# SparkFun_XBee_Arduino_Shield_Qwiic.net
KiCad netlist of a schematic drawn in EAGLE
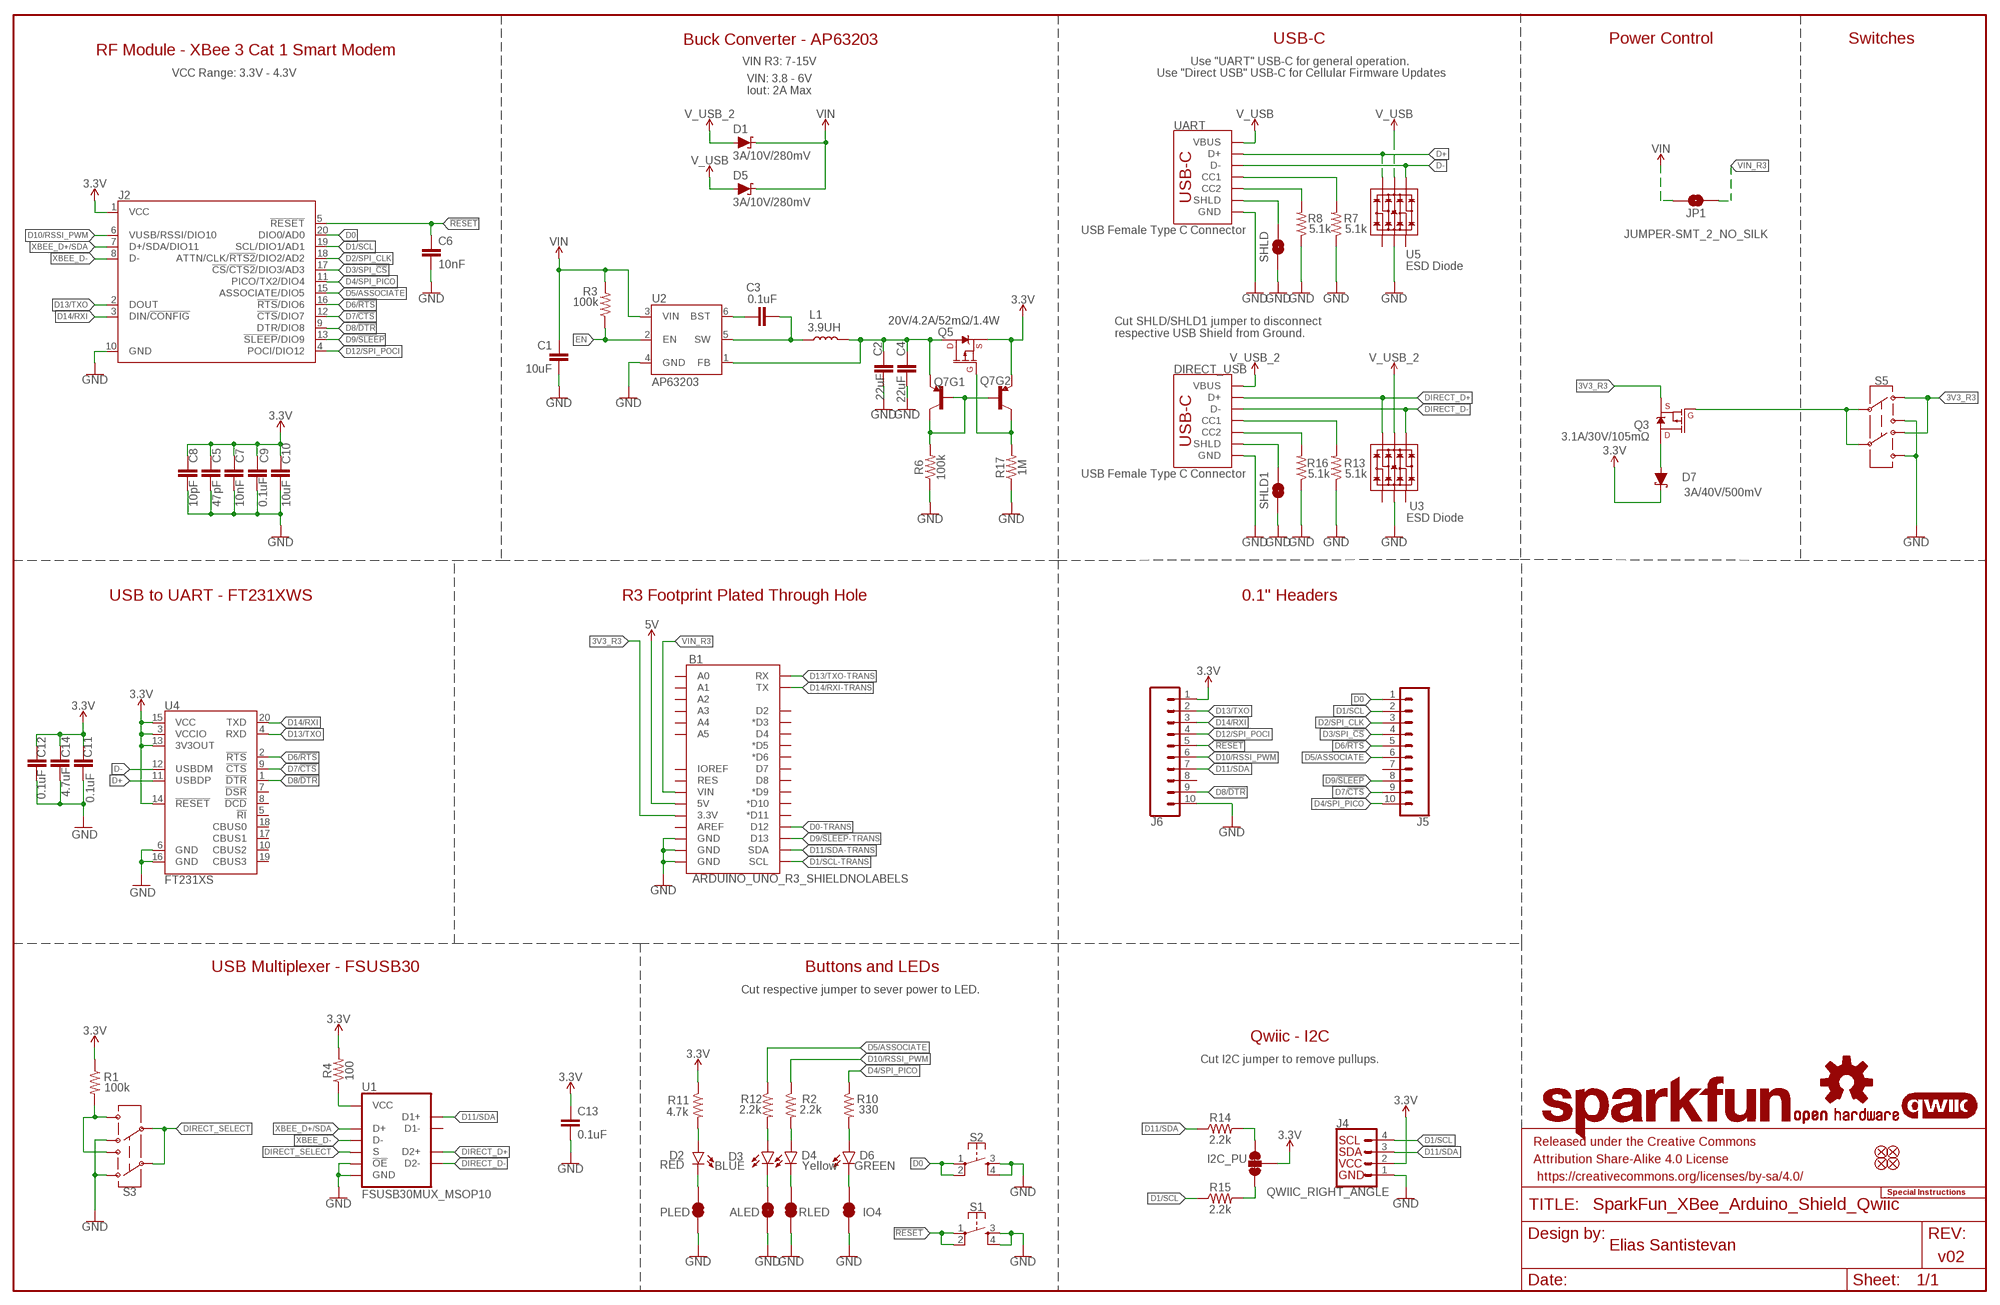
[diagram p0: schematic, sheet 1]

(export (version "E")
  (design (tool "Eeschema 10.0.6"))
  (components
    (comp (ref "ALED")
      (value "JUMPER-SMT_2_NC_TRACE_SILK")
      (footprint "eagle-import:SMT-JUMPER_2_NC_TRACE_SILK")
      (libsource (lib "eagle-import") (part "JUMPER-SMT_2_NC_TRACE_SILK"))
    )
    (comp (ref "B1")
      (value "ARDUINO_UNO_R3_SHIELDNOLABELS")
      (footprint "eagle-import:UNO_R3_SHIELD_NOLABELS")
      (libsource (lib "eagle-import") (part "ARDUINO_UNO_R3_SHIELDNOLABELS"))
    )
    (comp (ref "C1")
      (value "10uF")
      (footprint "eagle-import:1210")
      (libsource (lib "eagle-import") (part "10UF-1210-50V-20%"))
    )
    (comp (ref "C2")
      (value "22uF")
      (footprint "eagle-import:0603")
      (libsource (lib "eagle-import") (part "22UF-0603-6.3V-20%"))
    )
    (comp (ref "C3")
      (value "0.1uF")
      (footprint "eagle-import:0603")
      (libsource (lib "eagle-import") (part "0.1UF-0603-25V-5%"))
    )
    (comp (ref "C4")
      (value "22uF")
      (footprint "eagle-import:0603")
      (libsource (lib "eagle-import") (part "22UF-0603-6.3V-20%"))
    )
    (comp (ref "C5")
      (value "47pF")
      (footprint "eagle-import:0603")
      (libsource (lib "eagle-import") (part "47PF-0603-50V-5%"))
    )
    (comp (ref "C6")
      (value "10nF")
      (footprint "eagle-import:0603")
      (libsource (lib "eagle-import") (part "10NF-0603-50V-10%"))
    )
    (comp (ref "C7")
      (value "10nF")
      (footprint "eagle-import:0603")
      (libsource (lib "eagle-import") (part "10NF-0603-50V-10%"))
    )
    (comp (ref "C8")
      (value "10pF")
      (footprint "eagle-import:0603")
      (libsource (lib "eagle-import") (part "10PF-0603-50V-5%"))
    )
    (comp (ref "C9")
      (value "0.1uF")
      (footprint "eagle-import:0603")
      (libsource (lib "eagle-import") (part "0.1UF-0603-25V-(+80/-20%)"))
    )
    (comp (ref "C10")
      (value "10uF")
      (footprint "eagle-import:0603")
      (libsource (lib "eagle-import") (part "10UF-0603-6.3V-20%"))
    )
    (comp (ref "C11")
      (value "0.1uF")
      (footprint "eagle-import:0603")
      (libsource (lib "eagle-import") (part "0.1UF-0603-25V-(+80/-20%)"))
    )
    (comp (ref "C12")
      (value "0.1uF")
      (footprint "eagle-import:0603")
      (libsource (lib "eagle-import") (part "0.1UF-0603-25V-(+80/-20%)"))
    )
    (comp (ref "C13")
      (value "0.1uF")
      (footprint "eagle-import:0603")
      (libsource (lib "eagle-import") (part "0.1UF-0603-25V-(+80/-20%)"))
    )
    (comp (ref "C14")
      (value "4.7uF")
      (footprint "eagle-import:0603")
      (libsource (lib "eagle-import") (part "4.7UF-0603-6.3V-(10%)"))
    )
    (comp (ref "D1")
      (value "3A/10V/280mV")
      (footprint "eagle-import:SOD-323")
      (libsource (lib "eagle-import") (part "DIODE-SCHOTTKY-BAT60A"))
    )
    (comp (ref "D2")
      (value "RED")
      (footprint "eagle-import:LED-0603")
      (libsource (lib "eagle-import") (part "LED-RED_0603-KB"))
    )
    (comp (ref "D3")
      (value "BLUE")
      (footprint "eagle-import:LED-0603")
      (libsource (lib "eagle-import") (part "LED-BLUE0603"))
    )
    (comp (ref "D4")
      (value "Yellow")
      (footprint "eagle-import:LED-0603")
      (libsource (lib "eagle-import") (part "LED-YELLOW0603"))
    )
    (comp (ref "D5")
      (value "3A/10V/280mV")
      (footprint "eagle-import:SOD-323")
      (libsource (lib "eagle-import") (part "DIODE-SCHOTTKY-BAT60A"))
    )
    (comp (ref "D6")
      (value "GREEN")
      (footprint "eagle-import:LED-0603")
      (libsource (lib "eagle-import") (part "LED-GREEN0603"))
    )
    (comp (ref "D7")
      (value "3A/40V/500mV")
      (footprint "eagle-import:SMA-DIODE")
      (libsource (lib "eagle-import") (part "DIODE-SCHOTTKY-B340A"))
    )
    (comp (ref "DIRECT_USB")
      (value "USB Female Type C Connector")
      (footprint "eagle-import:USB-C-16P-4LAYER-ISOLATED")
      (libsource (lib "eagle-import") (part "USB_C_4-LAYER-ISOLATED"))
    )
    (comp (ref "FD1")
      (value "FIDUCIAL1X2")
      (footprint "eagle-import:FIDUCIAL-1X2")
      (libsource (lib "eagle-import") (part "FIDUCIAL1X2"))
    )
    (comp (ref "FD2")
      (value "FIDUCIAL1X2")
      (footprint "eagle-import:FIDUCIAL-1X2")
      (libsource (lib "eagle-import") (part "FIDUCIAL1X2"))
    )
    (comp (ref "FD3")
      (value "FIDUCIAL1X2")
      (footprint "eagle-import:FIDUCIAL-1X2")
      (libsource (lib "eagle-import") (part "FIDUCIAL1X2"))
    )
    (comp (ref "FD4")
      (value "FIDUCIAL1X2")
      (footprint "eagle-import:FIDUCIAL-1X2")
      (libsource (lib "eagle-import") (part "FIDUCIAL1X2"))
    )
    (comp (ref "FRAME1")
      (value "FRAME-LEDGER")
      (footprint "eagle-import:CREATIVE_COMMONS")
      (libsource (lib "eagle-import") (part "FRAME-LEDGER"))
    )
    (comp (ref "I2C_PU")
      (value "JUMPER-SMT_3_2-NC_TRACE_SILK")
      (footprint "eagle-import:SMT-JUMPER_3_2-NC_TRACE_SILK")
      (libsource (lib "eagle-import") (part "JUMPER-SMT_3_2-NC_TRACE_SILK"))
    )
    (comp (ref "IO4")
      (value "JUMPER-SMT_2_NC_TRACE_SILK")
      (footprint "eagle-import:SMT-JUMPER_2_NC_TRACE_SILK")
      (libsource (lib "eagle-import") (part "JUMPER-SMT_2_NC_TRACE_SILK"))
    )
    (comp (ref "J2")
      (value "XBEE_UPDATEXBEE_SMD")
      (footprint "eagle-import:XBEE3-SMD")
      (libsource (lib "eagle-import") (part "XBEE_UPDATEXBEE_SMD"))
    )
    (comp (ref "J4")
      (value "QWIIC_RIGHT_ANGLE")
      (footprint "eagle-import:JST04_1MM_RA")
      (libsource (lib "eagle-import") (part "QWIIC_CONNECTORJS-1MM"))
    )
    (comp (ref "J5")
      (value "CONN_10NO_SILK_PTH_FEMALE")
      (footprint "eagle-import:1X10_NO_SILK")
      (libsource (lib "eagle-import") (part "CONN_10NO_SILK_PTH_FEMALE"))
    )
    (comp (ref "J6")
      (value "CONN_10NO_SILK_PTH_FEMALE")
      (footprint "eagle-import:1X10_NO_SILK")
      (libsource (lib "eagle-import") (part "CONN_10NO_SILK_PTH_FEMALE"))
    )
    (comp (ref "JP1")
      (value "JUMPER-SMT_2_NO_SILK")
      (footprint "eagle-import:SMT-JUMPER_2_NO_SILK")
      (libsource (lib "eagle-import") (part "JUMPER-SMT_2_NO_SILK"))
    )
    (comp (ref "L1")
      (value "3.9UH")
      (footprint "eagle-import:INDUCTOR_3.9UH")
      (libsource (lib "eagle-import") (part "3.9UH"))
    )
    (comp (ref "LOGO1")
      (value "SFE_LOGO_NAMEBLANK")
      (footprint "eagle-import:BLANK")
      (libsource (lib "eagle-import") (part "SFE_LOGO_NAMEBLANK"))
    )
    (comp (ref "LOGO2")
      (value "OSHW-LOGOS")
      (footprint "eagle-import:OSHW-LOGO-S")
      (libsource (lib "eagle-import") (part "OSHW-LOGOS"))
    )
    (comp (ref "LOGO3")
      (value "QWIIC_LOGO_4MM")
      (footprint "eagle-import:QWIIC_4MM")
      (libsource (lib "eagle-import") (part "QWIIC_LOGO_4MM"))
    )
    (comp (ref "LOGO4")
      (value "SPECIAL_INSTRUCTIONS-ORDERING")
      (footprint "eagle-import:ORDERING_INSTRUCTIONS")
      (libsource (lib "eagle-import") (part "SPECIAL_INSTRUCTIONS-ORDERING"))
    )
    (comp (ref "PLED")
      (value "JUMPER-SMT_2_NC_TRACE_SILK")
      (footprint "eagle-import:SMT-JUMPER_2_NC_TRACE_SILK")
      (libsource (lib "eagle-import") (part "JUMPER-SMT_2_NC_TRACE_SILK"))
    )
    (comp (ref "Q3")
      (value "3.1A/30V/105mΩ")
      (footprint "eagle-import:SOT23-3")
      (libsource (lib "eagle-import") (part "MOSFET_PCH-DMG2307L"))
    )
    (comp (ref "Q5")
      (value "20V/4.2A/52mΩ/1.4W")
      (footprint "eagle-import:SOT23-3")
      (libsource (lib "eagle-import") (part "MOSFET_PCH-DMG2305UX-7"))
    )
    (comp (ref "Q7")
      (value "TRANS_PNP_DUALSOT-363")
      (footprint "eagle-import:SOT363_PHILIPS")
      (libsource (lib "eagle-import") (part "TRANS_PNP_DUALSOT-363"))
    )
    (comp (ref "R1")
      (value "100k")
      (footprint "eagle-import:0603")
      (libsource (lib "eagle-import") (part "100KOHM-0603-1/10W-1%"))
    )
    (comp (ref "R2")
      (value "2.2k")
      (footprint "eagle-import:0603")
      (libsource (lib "eagle-import") (part "2.2KOHM-0603-1/10W-1%"))
    )
    (comp (ref "R3")
      (value "100k")
      (footprint "eagle-import:0603")
      (libsource (lib "eagle-import") (part "100KOHM-0603-1/10W-1%"))
    )
    (comp (ref "R4")
      (value "100")
      (footprint "eagle-import:0603")
      (libsource (lib "eagle-import") (part "100OHM-0603-1/10W-1%"))
    )
    (comp (ref "R6")
      (value "100k")
      (footprint "eagle-import:0603")
      (libsource (lib "eagle-import") (part "100KOHM-0603-1/10W-1%"))
    )
    (comp (ref "R7")
      (value "5.1k")
      (footprint "eagle-import:0603")
      (libsource (lib "eagle-import") (part "5.1KOHM5.1KOHM-0603-1/10W-1%"))
    )
    (comp (ref "R8")
      (value "5.1k")
      (footprint "eagle-import:0603")
      (libsource (lib "eagle-import") (part "5.1KOHM5.1KOHM-0603-1/10W-1%"))
    )
    (comp (ref "R10")
      (value "330")
      (footprint "eagle-import:0603")
      (libsource (lib "eagle-import") (part "330OHM-0603-1/10W-1%"))
    )
    (comp (ref "R11")
      (value "4.7k")
      (footprint "eagle-import:0603")
      (libsource (lib "eagle-import") (part "4.7KOHM-0603-1/10W-1%"))
    )
    (comp (ref "R12")
      (value "2.2k")
      (footprint "eagle-import:0603")
      (libsource (lib "eagle-import") (part "2.2KOHM-0603-1/10W-1%"))
    )
    (comp (ref "R13")
      (value "5.1k")
      (footprint "eagle-import:0603")
      (libsource (lib "eagle-import") (part "5.1KOHM5.1KOHM-0603-1/10W-1%"))
    )
    (comp (ref "R14")
      (value "2.2k")
      (footprint "eagle-import:0603")
      (libsource (lib "eagle-import") (part "2.2KOHM-0603-1/10W-1%"))
    )
    (comp (ref "R15")
      (value "2.2k")
      (footprint "eagle-import:0603")
      (libsource (lib "eagle-import") (part "2.2KOHM-0603-1/10W-1%"))
    )
    (comp (ref "R16")
      (value "5.1k")
      (footprint "eagle-import:0603")
      (libsource (lib "eagle-import") (part "5.1KOHM5.1KOHM-0603-1/10W-1%"))
    )
    (comp (ref "R17")
      (value "1M")
      (footprint "eagle-import:0603")
      (libsource (lib "eagle-import") (part "1MOHM-0603-1/4W-5%"))
    )
    (comp (ref "RLED")
      (value "JUMPER-SMT_2_NC_TRACE_SILK")
      (footprint "eagle-import:SMT-JUMPER_2_NC_TRACE_SILK")
      (libsource (lib "eagle-import") (part "JUMPER-SMT_2_NC_TRACE_SILK"))
    )
    (comp (ref "S1")
      (value "MOMENTARY-SWITCH-SPST-2-SMD-5.2MM-TALL")
      (footprint "eagle-import:TACTILE_SWITCH_SMD_5.2MM")
      (libsource (lib "eagle-import") (part "MOMENTARY-SWITCH-SPST-2-SMD-5.2MM-TALL"))
    )
    (comp (ref "S2")
      (value "MOMENTARY-SWITCH-SPST-2-SMD-5.2MM-TALL")
      (footprint "eagle-import:TACTILE_SWITCH_SMD_5.2MM")
      (libsource (lib "eagle-import") (part "MOMENTARY-SWITCH-SPST-2-SMD-5.2MM-TALL"))
    )
    (comp (ref "S3")
      (value "SWITCH-DPDT-SMD-AYZ0202")
      (footprint "eagle-import:SWITCH_DPDT_SMD_AYZ0202")
      (libsource (lib "eagle-import") (part "SWITCH-DPDT-SMD-AYZ0202"))
    )
    (comp (ref "S5")
      (value "SWITCH-DPDT-SMD-AYZ0202")
      (footprint "eagle-import:SWITCH_DPDT_SMD_AYZ0202")
      (libsource (lib "eagle-import") (part "SWITCH-DPDT-SMD-AYZ0202"))
    )
    (comp (ref "SHLD")
      (value "JUMPER-SMT_2_NC_TRACE_SILK")
      (footprint "eagle-import:SMT-JUMPER_2_NC_TRACE_SILK")
      (libsource (lib "eagle-import") (part "JUMPER-SMT_2_NC_TRACE_SILK"))
    )
    (comp (ref "SHLD1")
      (value "JUMPER-SMT_2_NC_TRACE_SILK")
      (footprint "eagle-import:SMT-JUMPER_2_NC_TRACE_SILK")
      (libsource (lib "eagle-import") (part "JUMPER-SMT_2_NC_TRACE_SILK"))
    )
    (comp (ref "U1")
      (value "FSUSB30MUX_MSOP10")
      (footprint "eagle-import:MSOP10")
      (libsource (lib "eagle-import") (part "FSUSB30MUX_MSOP10"))
    )
    (comp (ref "U2")
      (value "AP63203")
      (footprint "eagle-import:SOT23-6")
      (libsource (lib "eagle-import") (part "AP63203"))
    )
    (comp (ref "U3")
      (value "ESD Diode")
      (footprint "eagle-import:SOT-23-6")
      (libsource (lib "eagle-import") (part "TVS_DIODE_ARRAY_DT1042-04SO-7"))
    )
    (comp (ref "U4")
      (value "FT231XS")
      (footprint "eagle-import:SSOP20_L")
      (libsource (lib "eagle-import") (part "FT231XS"))
    )
    (comp (ref "U5")
      (value "ESD Diode")
      (footprint "eagle-import:SOT-23-6")
      (libsource (lib "eagle-import") (part "TVS_DIODE_ARRAY_DT1042-04SO-7"))
    )
    (comp (ref "UART")
      (value "USB Female Type C Connector")
      (footprint "eagle-import:USB-C-16P-4LAYER-ISOLATED")
      (libsource (lib "eagle-import") (part "USB_C_4-LAYER-ISOLATED"))
    )
  )
  (nets
    (net (code "1") (name "/D3{slash}SPI_~{CS}") (class "Default")
      (node (ref "J2") (pin "17") (pinfunction "~{CS}/~{CTS2}/DIO3/AD3_17") (pintype "bidirectional"))
      (node (ref "J5") (pin "4") (pinfunction "4_4") (pintype "passive"))
    )
    (net (code "2") (name "/D6{slash}~{RTS}") (class "Default")
      (node (ref "J2") (pin "16") (pinfunction "~{RTS}/DIO6_16") (pintype "input"))
      (node (ref "J5") (pin "5") (pinfunction "5_5") (pintype "passive"))
      (node (ref "U4") (pin "2") (pinfunction "~{RTS}_2") (pintype "bidirectional"))
    )
    (net (code "3") (name "/D7{slash}~{CTS}") (class "Default")
      (node (ref "J2") (pin "12") (pinfunction "~{CTS}/DIO7_12") (pintype "output"))
      (node (ref "J5") (pin "9") (pinfunction "9_9") (pintype "passive"))
      (node (ref "U4") (pin "9") (pinfunction "~{CTS}_9") (pintype "bidirectional"))
    )
    (net (code "4") (name "/D8{slash}~{DTR}") (class "Default")
      (node (ref "J2") (pin "9") (pinfunction "DTR/DIO8_9") (pintype "bidirectional"))
      (node (ref "J6") (pin "9") (pinfunction "9_9") (pintype "passive"))
      (node (ref "U4") (pin "1") (pinfunction "~{DTR}_1") (pintype "bidirectional"))
    )
    (net (code "5") (name "/D9{slash}~{SLEEP}") (class "Default")
      (node (ref "J2") (pin "13") (pinfunction "~{SLEEP}/DIO9_13") (pintype "bidirectional"))
      (node (ref "J5") (pin "8") (pinfunction "8_8") (pintype "passive"))
    )
    (net (code "6") (name "/D9{slash}~{SLEEP}-TRANS") (class "Default")
      (node (ref "B1") (pin "D13") (pinfunction "D13_D13") (pintype "bidirectional"))
    )
    (net (code "7") (name "/~{RESET}") (class "Default")
      (node (ref "C6") (pin "1") (pinfunction "1_1") (pintype "passive"))
      (node (ref "J2") (pin "5") (pinfunction "~{RESET}_5") (pintype "input"))
      (node (ref "J6") (pin "5") (pinfunction "5_5") (pintype "passive"))
      (node (ref "S1") (pin "1") (pinfunction "1_1") (pintype "passive"))
      (node (ref "S1") (pin "2") (pinfunction "2_2") (pintype "passive"))
    )
    (net (code "8") (name "3.3V") (class "Default")
      (node (ref "C10") (pin "1") (pinfunction "1_1") (pintype "passive"))
      (node (ref "C11") (pin "1") (pinfunction "1_1") (pintype "passive"))
      (node (ref "C12") (pin "1") (pinfunction "1_1") (pintype "passive"))
      (node (ref "C13") (pin "1") (pinfunction "1_1") (pintype "passive"))
      (node (ref "C14") (pin "1") (pinfunction "1_1") (pintype "passive"))
      (node (ref "C5") (pin "1") (pinfunction "1_1") (pintype "passive"))
      (node (ref "C7") (pin "1") (pinfunction "1_1") (pintype "passive"))
      (node (ref "C8") (pin "1") (pinfunction "1_1") (pintype "passive"))
      (node (ref "C9") (pin "1") (pinfunction "1_1") (pintype "passive"))
      (node (ref "D7") (pin "C") (pinfunction "C_C") (pintype "passive"))
      (node (ref "I2C_PU") (pin "2") (pinfunction "2_2") (pintype "passive"))
      (node (ref "J2") (pin "1") (pinfunction "VCC_1") (pintype "power_in"))
      (node (ref "J4") (pin "2") (pinfunction "2_2") (pintype "power_in"))
      (node (ref "J6") (pin "1") (pinfunction "1_1") (pintype "passive"))
      (node (ref "Q5") (pin "2") (pinfunction "S_2") (pintype "bidirectional"))
      (node (ref "Q7") (pin "4") (pinfunction "E_4") (pintype "passive"))
      (node (ref "R1") (pin "1") (pinfunction "1_1") (pintype "passive"))
      (node (ref "R11") (pin "1") (pinfunction "1_1") (pintype "passive"))
      (node (ref "R4") (pin "2") (pinfunction "2_2") (pintype "passive"))
      (node (ref "U4") (pin "13") (pinfunction "3V3OUT_13") (pintype "bidirectional"))
      (node (ref "U4") (pin "14") (pinfunction "~{RESET}_14") (pintype "bidirectional"))
      (node (ref "U4") (pin "15") (pinfunction "VCC_15") (pintype "bidirectional"))
      (node (ref "U4") (pin "3") (pinfunction "VCCIO_3") (pintype "bidirectional"))
    )
    (net (code "9") (name "3V3_R3") (class "Default")
      (node (ref "B1") (pin "3.3V") (pinfunction "3.3V_3.3V") (pintype "bidirectional"))
      (node (ref "Q3") (pin "2") (pinfunction "S_2") (pintype "bidirectional"))
      (node (ref "S5") (pin "3") (pinfunction "3_3") (pintype "bidirectional"))
      (node (ref "S5") (pin "6") (pinfunction "6_6") (pintype "bidirectional"))
    )
    (net (code "10") (name "5V") (class "Default")
      (node (ref "B1") (pin "5V") (pinfunction "5V_5V") (pintype "bidirectional"))
    )
    (net (code "11") (name "D+") (class "Default")
      (node (ref "U4") (pin "11") (pinfunction "USBDP_11") (pintype "bidirectional"))
      (node (ref "U5") (pin "6") (pinfunction "IO4_6") (pintype "bidirectional"))
      (node (ref "UART") (pin "A6") (pinfunction "D+_A6") (pintype "bidirectional"))
      (node (ref "UART") (pin "B6") (pinfunction "D+_B6") (pintype "bidirectional"))
    )
    (net (code "12") (name "D-") (class "Default")
      (node (ref "U4") (pin "12") (pinfunction "USBDM_12") (pintype "bidirectional"))
      (node (ref "U5") (pin "4") (pinfunction "IO3_4") (pintype "bidirectional"))
      (node (ref "UART") (pin "A7") (pinfunction "D-_A7") (pintype "bidirectional"))
      (node (ref "UART") (pin "B7") (pinfunction "D-_B7") (pintype "bidirectional"))
    )
    (net (code "13") (name "D0") (class "Default")
      (node (ref "J2") (pin "20") (pinfunction "DIO0/AD0_20") (pintype "bidirectional"))
      (node (ref "J5") (pin "1") (pinfunction "1_1") (pintype "passive"))
      (node (ref "S2") (pin "1") (pinfunction "1_1") (pintype "passive"))
      (node (ref "S2") (pin "2") (pinfunction "2_2") (pintype "passive"))
    )
    (net (code "14") (name "D0-TRANS") (class "Default")
      (node (ref "B1") (pin "D12") (pinfunction "D12_D12") (pintype "bidirectional"))
    )
    (net (code "15") (name "D1{slash}SCL") (class "Default")
      (node (ref "J2") (pin "19") (pinfunction "SCL/DIO1/AD1_19") (pintype "bidirectional"))
      (node (ref "J4") (pin "4") (pinfunction "4_4") (pintype "passive"))
      (node (ref "J5") (pin "2") (pinfunction "2_2") (pintype "passive"))
      (node (ref "R15") (pin "1") (pinfunction "1_1") (pintype "passive"))
    )
    (net (code "16") (name "D1{slash}SCL-TRANS") (class "Default")
      (node (ref "B1") (pin "SCL") (pinfunction "SCL_SCL") (pintype "bidirectional"))
    )
    (net (code "17") (name "D2{slash}SPI_CLK") (class "Default")
      (node (ref "J2") (pin "18") (pinfunction "ATTN/CLK/~{RTS2}/DIO2/AD2_18") (pintype "bidirectional"))
      (node (ref "J5") (pin "3") (pinfunction "3_3") (pintype "passive"))
    )
    (net (code "18") (name "D4{slash}SPI_PICO") (class "Default")
      (node (ref "J2") (pin "11") (pinfunction "PICO/TX2/DIO4_11") (pintype "bidirectional"))
      (node (ref "J5") (pin "10") (pinfunction "10_10") (pintype "passive"))
      (node (ref "R10") (pin "1") (pinfunction "1_1") (pintype "passive"))
    )
    (net (code "19") (name "D5{slash}ASSOCIATE") (class "Default")
      (node (ref "J2") (pin "15") (pinfunction "ASSOCIATE/DIO5_15") (pintype "bidirectional"))
      (node (ref "J5") (pin "6") (pinfunction "6_6") (pintype "passive"))
      (node (ref "R12") (pin "1") (pinfunction "1_1") (pintype "passive"))
    )
    (net (code "20") (name "D10{slash}RSSI_PWM") (class "Default")
      (node (ref "J2") (pin "6") (pinfunction "VUSB/RSSI/DIO10_6") (pintype "bidirectional"))
      (node (ref "J6") (pin "6") (pinfunction "6_6") (pintype "passive"))
      (node (ref "R2") (pin "1") (pinfunction "1_1") (pintype "passive"))
    )
    (net (code "21") (name "D11{slash}SDA") (class "Default")
      (node (ref "J4") (pin "3") (pinfunction "3_3") (pintype "passive"))
      (node (ref "J6") (pin "7") (pinfunction "7_7") (pintype "passive"))
      (node (ref "R14") (pin "1") (pinfunction "1_1") (pintype "passive"))
      (node (ref "U1") (pin "2") (pinfunction "D1+_2") (pintype "bidirectional"))
    )
    (net (code "22") (name "D11{slash}SDA-TRANS") (class "Default")
      (node (ref "B1") (pin "SDA") (pinfunction "SDA_SDA") (pintype "bidirectional"))
    )
    (net (code "23") (name "D12{slash}SPI_POCI") (class "Default")
      (node (ref "J2") (pin "4") (pinfunction "POCI/DIO12_4") (pintype "bidirectional"))
      (node (ref "J6") (pin "4") (pinfunction "4_4") (pintype "passive"))
    )
    (net (code "24") (name "D13{slash}TXO") (class "Default")
      (node (ref "J2") (pin "2") (pinfunction "DOUT_2") (pintype "output"))
      (node (ref "J6") (pin "2") (pinfunction "2_2") (pintype "passive"))
      (node (ref "U4") (pin "4") (pinfunction "RXD_4") (pintype "bidirectional"))
    )
    (net (code "25") (name "D13{slash}TXO-TRANS") (class "Default")
      (node (ref "B1") (pin "RX") (pinfunction "RX_RX") (pintype "bidirectional"))
    )
    (net (code "26") (name "D14{slash}RXI") (class "Default")
      (node (ref "J2") (pin "3") (pinfunction "DIN/~{CONFIG}_3") (pintype "input"))
      (node (ref "J6") (pin "3") (pinfunction "3_3") (pintype "passive"))
      (node (ref "U4") (pin "20") (pinfunction "TXD_20") (pintype "bidirectional"))
    )
    (net (code "27") (name "D14{slash}RXI-TRANS") (class "Default")
      (node (ref "B1") (pin "TX") (pinfunction "TX_TX") (pintype "bidirectional"))
    )
    (net (code "28") (name "DIRECT_D+") (class "Default")
      (node (ref "DIRECT_USB") (pin "A6") (pinfunction "D+_A6") (pintype "bidirectional"))
      (node (ref "DIRECT_USB") (pin "B6") (pinfunction "D+_B6") (pintype "bidirectional"))
      (node (ref "U1") (pin "3") (pinfunction "D2+_3") (pintype "bidirectional"))
      (node (ref "U3") (pin "6") (pinfunction "IO4_6") (pintype "bidirectional"))
    )
    (net (code "29") (name "DIRECT_D-") (class "Default")
      (node (ref "DIRECT_USB") (pin "A7") (pinfunction "D-_A7") (pintype "bidirectional"))
      (node (ref "DIRECT_USB") (pin "B7") (pinfunction "D-_B7") (pintype "bidirectional"))
      (node (ref "U1") (pin "7") (pinfunction "D2-_7") (pintype "bidirectional"))
      (node (ref "U3") (pin "4") (pinfunction "IO3_4") (pintype "bidirectional"))
    )
    (net (code "30") (name "DIRECT_SELECT") (class "Default")
      (node (ref "S3") (pin "2") (pinfunction "2_2") (pintype "bidirectional"))
      (node (ref "S3") (pin "5") (pinfunction "5_5") (pintype "bidirectional"))
      (node (ref "U1") (pin "1") (pinfunction "S_1") (pintype "bidirectional"))
    )
    (net (code "31") (name "EN") (class "Default")
      (node (ref "R3") (pin "1") (pinfunction "1_1") (pintype "passive"))
      (node (ref "U2") (pin "2") (pinfunction "EN_2") (pintype "bidirectional"))
    )
    (net (code "32") (name "GND") (class "Default")
      (node (ref "ALED") (pin "1") (pinfunction "1_1") (pintype "passive"))
      (node (ref "B1") (pin "GND@0") (pinfunction "GND_GND@0") (pintype "bidirectional"))
      (node (ref "B1") (pin "GND@1") (pinfunction "GND_GND@1") (pintype "bidirectional"))
      (node (ref "B1") (pin "GND@2") (pinfunction "GND_GND@2") (pintype "bidirectional"))
      (node (ref "C1") (pin "2") (pinfunction "2_2") (pintype "passive"))
      (node (ref "C10") (pin "2") (pinfunction "2_2") (pintype "passive"))
      (node (ref "C11") (pin "2") (pinfunction "2_2") (pintype "passive"))
      (node (ref "C12") (pin "2") (pinfunction "2_2") (pintype "passive"))
      (node (ref "C13") (pin "2") (pinfunction "2_2") (pintype "passive"))
      (node (ref "C14") (pin "2") (pinfunction "2_2") (pintype "passive"))
      (node (ref "C2") (pin "2") (pinfunction "2_2") (pintype "passive"))
      (node (ref "C4") (pin "2") (pinfunction "2_2") (pintype "passive"))
      (node (ref "C5") (pin "2") (pinfunction "2_2") (pintype "passive"))
      (node (ref "C6") (pin "2") (pinfunction "2_2") (pintype "passive"))
      (node (ref "C7") (pin "2") (pinfunction "2_2") (pintype "passive"))
      (node (ref "C8") (pin "2") (pinfunction "2_2") (pintype "passive"))
      (node (ref "C9") (pin "2") (pinfunction "2_2") (pintype "passive"))
      (node (ref "DIRECT_USB") (pin "GND") (pinfunction "GND_GND") (pintype "bidirectional"))
      (node (ref "DIRECT_USB") (pin "GND2") (pinfunction "GND_GND2") (pintype "bidirectional"))
      (node (ref "IO4") (pin "1") (pinfunction "1_1") (pintype "passive"))
      (node (ref "J2") (pin "10") (pinfunction "GND_10") (pintype "power_in"))
      (node (ref "J4") (pin "1") (pinfunction "1_1") (pintype "power_in"))
      (node (ref "J6") (pin "10") (pinfunction "10_10") (pintype "passive"))
      (node (ref "PLED") (pin "1") (pinfunction "1_1") (pintype "passive"))
      (node (ref "R13") (pin "1") (pinfunction "1_1") (pintype "passive"))
      (node (ref "R16") (pin "1") (pinfunction "1_1") (pintype "passive"))
      (node (ref "R17") (pin "1") (pinfunction "1_1") (pintype "passive"))
      (node (ref "R6") (pin "1") (pinfunction "1_1") (pintype "passive"))
      (node (ref "R7") (pin "1") (pinfunction "1_1") (pintype "passive"))
      (node (ref "R8") (pin "1") (pinfunction "1_1") (pintype "passive"))
      (node (ref "RLED") (pin "1") (pinfunction "1_1") (pintype "passive"))
      (node (ref "S1") (pin "3") (pinfunction "3_3") (pintype "passive"))
      (node (ref "S1") (pin "4") (pinfunction "4_4") (pintype "passive"))
      (node (ref "S2") (pin "3") (pinfunction "3_3") (pintype "passive"))
      (node (ref "S2") (pin "4") (pinfunction "4_4") (pintype "passive"))
      (node (ref "S3") (pin "3") (pinfunction "3_3") (pintype "bidirectional"))
      (node (ref "S3") (pin "6") (pinfunction "6_6") (pintype "bidirectional"))
      (node (ref "S5") (pin "1") (pinfunction "1_1") (pintype "bidirectional"))
      (node (ref "S5") (pin "4") (pinfunction "4_4") (pintype "bidirectional"))
      (node (ref "SHLD") (pin "1") (pinfunction "1_1") (pintype "passive"))
      (node (ref "SHLD1") (pin "1") (pinfunction "1_1") (pintype "passive"))
      (node (ref "U1") (pin "5") (pinfunction "GND_5") (pintype "bidirectional"))
      (node (ref "U1") (pin "9") (pinfunction "~{OE}_9") (pintype "bidirectional"))
      (node (ref "U2") (pin "4") (pinfunction "GND_4") (pintype "bidirectional"))
      (node (ref "U3") (pin "2") (pinfunction "VSS_2") (pintype "bidirectional"))
      (node (ref "U4") (pin "16") (pinfunction "GND_16") (pintype "bidirectional"))
      (node (ref "U4") (pin "6") (pinfunction "GND_6") (pintype "bidirectional"))
      (node (ref "U5") (pin "2") (pinfunction "VSS_2") (pintype "bidirectional"))
      (node (ref "UART") (pin "GND") (pinfunction "GND_GND") (pintype "bidirectional"))
      (node (ref "UART") (pin "GND2") (pinfunction "GND_GND2") (pintype "bidirectional"))
    )
    (net (code "33") (name "Net-(ALED-Pad2)") (class "Default")
      (node (ref "ALED") (pin "2") (pinfunction "2_2") (pintype "passive"))
      (node (ref "D3") (pin "C") (pinfunction "C_C") (pintype "passive"))
    )
    (net (code "34") (name "Net-(D2-PadA)") (class "Default")
      (node (ref "D2") (pin "A") (pinfunction "A_A") (pintype "passive"))
      (node (ref "R11") (pin "2") (pinfunction "2_2") (pintype "passive"))
    )
    (net (code "35") (name "Net-(D2-PadC)") (class "Default")
      (node (ref "D2") (pin "C") (pinfunction "C_C") (pintype "passive"))
      (node (ref "PLED") (pin "2") (pinfunction "2_2") (pintype "passive"))
    )
    (net (code "36") (name "Net-(D3-PadA)") (class "Default")
      (node (ref "D3") (pin "A") (pinfunction "A_A") (pintype "passive"))
      (node (ref "R12") (pin "2") (pinfunction "2_2") (pintype "passive"))
    )
    (net (code "37") (name "Net-(D4-PadA)") (class "Default")
      (node (ref "D4") (pin "A") (pinfunction "A_A") (pintype "passive"))
      (node (ref "R2") (pin "2") (pinfunction "2_2") (pintype "passive"))
    )
    (net (code "38") (name "Net-(D4-PadC)") (class "Default")
      (node (ref "D4") (pin "C") (pinfunction "C_C") (pintype "passive"))
      (node (ref "RLED") (pin "2") (pinfunction "2_2") (pintype "passive"))
    )
    (net (code "39") (name "Net-(D6-PadA)") (class "Default")
      (node (ref "D6") (pin "A") (pinfunction "A_A") (pintype "passive"))
      (node (ref "R10") (pin "2") (pinfunction "2_2") (pintype "passive"))
    )
    (net (code "40") (name "Net-(D6-PadC)") (class "Default")
      (node (ref "D6") (pin "C") (pinfunction "C_C") (pintype "passive"))
      (node (ref "IO4") (pin "2") (pinfunction "2_2") (pintype "passive"))
    )
    (net (code "41") (name "Net-(DIRECT_USB-CC1)") (class "Default")
      (node (ref "DIRECT_USB") (pin "A5") (pinfunction "CC1_A5") (pintype "bidirectional"))
      (node (ref "R13") (pin "2") (pinfunction "2_2") (pintype "passive"))
    )
    (net (code "42") (name "Net-(DIRECT_USB-CC2)") (class "Default")
      (node (ref "DIRECT_USB") (pin "B5") (pinfunction "CC2_B5") (pintype "bidirectional"))
      (node (ref "R16") (pin "2") (pinfunction "2_2") (pintype "passive"))
    )
    (net (code "43") (name "Net-(DIRECT_USB-SHLD-PadSHLD1)") (class "Default")
      (node (ref "DIRECT_USB") (pin "SHLD1") (pinfunction "SHLD_SHLD1") (pintype "bidirectional"))
      (node (ref "DIRECT_USB") (pin "SHLD2") (pinfunction "SHLD_SHLD2") (pintype "bidirectional"))
      (node (ref "DIRECT_USB") (pin "SHLD3") (pinfunction "SHLD_SHLD3") (pintype "bidirectional"))
      (node (ref "DIRECT_USB") (pin "SHLD4") (pinfunction "SHLD_SHLD4") (pintype "bidirectional"))
      (node (ref "DIRECT_USB") (pin "SHLD5") (pinfunction "SHLD_SHLD5") (pintype "bidirectional"))
      (node (ref "DIRECT_USB") (pin "SHLD6") (pinfunction "SHLD_SHLD6") (pintype "bidirectional"))
      (node (ref "DIRECT_USB") (pin "SHLD7") (pinfunction "SHLD_SHLD7") (pintype "bidirectional"))
      (node (ref "DIRECT_USB") (pin "SHLD8") (pinfunction "SHLD_SHLD8") (pintype "bidirectional"))
      (node (ref "SHLD1") (pin "2") (pinfunction "2_2") (pintype "passive"))
    )
    (net (code "44") (name "Net-(I2C_PU-Pad1)") (class "Default")
      (node (ref "I2C_PU") (pin "1") (pinfunction "1_1") (pintype "passive"))
      (node (ref "R15") (pin "2") (pinfunction "2_2") (pintype "passive"))
    )
    (net (code "45") (name "Net-(I2C_PU-Pad3)") (class "Default")
      (node (ref "I2C_PU") (pin "3") (pinfunction "3_3") (pintype "passive"))
      (node (ref "R14") (pin "2") (pinfunction "2_2") (pintype "passive"))
    )
    (net (code "46") (name "Net-(L1-1)") (class "Default")
      (node (ref "C3") (pin "2") (pinfunction "2_2") (pintype "passive"))
      (node (ref "L1") (pin "P$1") (pinfunction "1_P$1") (pintype "passive"))
      (node (ref "U2") (pin "5") (pinfunction "SW_5") (pintype "bidirectional"))
    )
    (net (code "47") (name "Net-(L1-2)") (class "Default")
      (node (ref "C2") (pin "1") (pinfunction "1_1") (pintype "passive"))
      (node (ref "C4") (pin "1") (pinfunction "1_1") (pintype "passive"))
      (node (ref "L1") (pin "P$2") (pinfunction "2_P$2") (pintype "passive"))
      (node (ref "Q5") (pin "3") (pinfunction "D_3") (pintype "bidirectional"))
      (node (ref "Q7") (pin "1") (pinfunction "E_1") (pintype "passive"))
      (node (ref "U2") (pin "1") (pinfunction "FB_1") (pintype "bidirectional"))
    )
    (net (code "48") (name "Net-(Q3-D)") (class "Default")
      (node (ref "D7") (pin "A") (pinfunction "A_A") (pintype "passive"))
      (node (ref "Q3") (pin "3") (pinfunction "D_3") (pintype "bidirectional"))
    )
    (net (code "49") (name "Net-(Q3-G)") (class "Default")
      (node (ref "Q3") (pin "1") (pinfunction "G_1") (pintype "bidirectional"))
      (node (ref "S5") (pin "2") (pinfunction "2_2") (pintype "bidirectional"))
      (node (ref "S5") (pin "5") (pinfunction "5_5") (pintype "bidirectional"))
    )
    (net (code "50") (name "Net-(Q5-G)") (class "Default")
      (node (ref "Q5") (pin "1") (pinfunction "G_1") (pintype "bidirectional"))
      (node (ref "Q7") (pin "3") (pinfunction "C_3") (pintype "passive"))
      (node (ref "R17") (pin "2") (pinfunction "2_2") (pintype "passive"))
    )
    (net (code "51") (name "Net-(Q7A-B)") (class "Default")
      (node (ref "Q7") (pin "2") (pinfunction "B_2") (pintype "passive"))
      (node (ref "Q7") (pin "5") (pinfunction "B_5") (pintype "passive"))
      (node (ref "Q7") (pin "6") (pinfunction "C_6") (pintype "passive"))
      (node (ref "R6") (pin "2") (pinfunction "2_2") (pintype "passive"))
    )
    (net (code "52") (name "Net-(R1-Pad2)") (class "Default")
      (node (ref "R1") (pin "2") (pinfunction "2_2") (pintype "passive"))
      (node (ref "S3") (pin "1") (pinfunction "1_1") (pintype "bidirectional"))
      (node (ref "S3") (pin "4") (pinfunction "4_4") (pintype "bidirectional"))
    )
    (net (code "53") (name "Net-(SHLD-Pad2)") (class "Default")
      (node (ref "SHLD") (pin "2") (pinfunction "2_2") (pintype "passive"))
      (node (ref "UART") (pin "SHLD1") (pinfunction "SHLD_SHLD1") (pintype "bidirectional"))
      (node (ref "UART") (pin "SHLD2") (pinfunction "SHLD_SHLD2") (pintype "bidirectional"))
      (node (ref "UART") (pin "SHLD3") (pinfunction "SHLD_SHLD3") (pintype "bidirectional"))
      (node (ref "UART") (pin "SHLD4") (pinfunction "SHLD_SHLD4") (pintype "bidirectional"))
      (node (ref "UART") (pin "SHLD5") (pinfunction "SHLD_SHLD5") (pintype "bidirectional"))
      (node (ref "UART") (pin "SHLD6") (pinfunction "SHLD_SHLD6") (pintype "bidirectional"))
      (node (ref "UART") (pin "SHLD7") (pinfunction "SHLD_SHLD7") (pintype "bidirectional"))
      (node (ref "UART") (pin "SHLD8") (pinfunction "SHLD_SHLD8") (pintype "bidirectional"))
    )
    (net (code "54") (name "Net-(U1-VCC)") (class "Default")
      (node (ref "R4") (pin "1") (pinfunction "1_1") (pintype "passive"))
      (node (ref "U1") (pin "10") (pinfunction "VCC_10") (pintype "bidirectional"))
    )
    (net (code "55") (name "Net-(U2-BST)") (class "Default")
      (node (ref "C3") (pin "1") (pinfunction "1_1") (pintype "passive"))
      (node (ref "U2") (pin "6") (pinfunction "BST_6") (pintype "bidirectional"))
    )
    (net (code "56") (name "Net-(UART-CC1)") (class "Default")
      (node (ref "R7") (pin "2") (pinfunction "2_2") (pintype "passive"))
      (node (ref "UART") (pin "A5") (pinfunction "CC1_A5") (pintype "bidirectional"))
    )
    (net (code "57") (name "Net-(UART-CC2)") (class "Default")
      (node (ref "R8") (pin "2") (pinfunction "2_2") (pintype "passive"))
      (node (ref "UART") (pin "B5") (pinfunction "CC2_B5") (pintype "bidirectional"))
    )
    (net (code "58") (name "VIN") (class "Default")
      (node (ref "C1") (pin "1") (pinfunction "1_1") (pintype "passive"))
      (node (ref "D1") (pin "C") (pinfunction "C_C") (pintype "passive"))
      (node (ref "D5") (pin "C") (pinfunction "C_C") (pintype "passive"))
      (node (ref "JP1") (pin "2") (pinfunction "2_2") (pintype "passive"))
      (node (ref "R3") (pin "2") (pinfunction "2_2") (pintype "passive"))
      (node (ref "U2") (pin "3") (pinfunction "VIN_3") (pintype "bidirectional"))
    )
    (net (code "59") (name "VIN_R3") (class "Default")
      (node (ref "B1") (pin "VIN") (pinfunction "VIN_VIN") (pintype "bidirectional"))
      (node (ref "JP1") (pin "1") (pinfunction "1_1") (pintype "passive"))
    )
    (net (code "60") (name "V_USB") (class "Default")
      (node (ref "D5") (pin "A") (pinfunction "A_A") (pintype "passive"))
      (node (ref "U5") (pin "5") (pinfunction "VCC_5") (pintype "bidirectional"))
      (node (ref "UART") (pin "VBUS1") (pinfunction "VBUS_VBUS1") (pintype "bidirectional"))
      (node (ref "UART") (pin "VBUS2") (pinfunction "VBUS_VBUS2") (pintype "bidirectional"))
    )
    (net (code "61") (name "V_USB_2") (class "Default")
      (node (ref "D1") (pin "A") (pinfunction "A_A") (pintype "passive"))
      (node (ref "DIRECT_USB") (pin "VBUS1") (pinfunction "VBUS_VBUS1") (pintype "bidirectional"))
      (node (ref "DIRECT_USB") (pin "VBUS2") (pinfunction "VBUS_VBUS2") (pintype "bidirectional"))
      (node (ref "U3") (pin "5") (pinfunction "VCC_5") (pintype "bidirectional"))
    )
    (net (code "62") (name "XBEE_D+{slash}SDA") (class "Default")
      (node (ref "J2") (pin "7") (pinfunction "D+/SDA/DIO11_7") (pintype "bidirectional"))
      (node (ref "U1") (pin "4") (pinfunction "D+_4") (pintype "bidirectional"))
    )
    (net (code "63") (name "XBEE_D-") (class "Default")
      (node (ref "J2") (pin "8") (pinfunction "D-_8") (pintype "bidirectional"))
      (node (ref "U1") (pin "6") (pinfunction "D-_6") (pintype "bidirectional"))
    )
    (net (code "64") (name "unconnected-(B1-*D3-PadD3)") (class "Default")
      (node (ref "B1") (pin "D3") (pinfunction "*D3_D3") (pintype "bidirectional"))
    )
    (net (code "65") (name "unconnected-(B1-*D5-PadD5)") (class "Default")
      (node (ref "B1") (pin "D5") (pinfunction "*D5_D5") (pintype "bidirectional"))
    )
    (net (code "66") (name "unconnected-(B1-*D6-PadD6)") (class "Default")
      (node (ref "B1") (pin "D6") (pinfunction "*D6_D6") (pintype "bidirectional"))
    )
    (net (code "67") (name "unconnected-(B1-*D9-PadD9)") (class "Default")
      (node (ref "B1") (pin "D9") (pinfunction "*D9_D9") (pintype "bidirectional"))
    )
    (net (code "68") (name "unconnected-(B1-*D10-PadD10)") (class "Default")
      (node (ref "B1") (pin "D10") (pinfunction "*D10_D10") (pintype "bidirectional"))
    )
    (net (code "69") (name "unconnected-(B1-*D11-PadD11)") (class "Default")
      (node (ref "B1") (pin "D11") (pinfunction "*D11_D11") (pintype "bidirectional"))
    )
    (net (code "70") (name "unconnected-(B1-PadA0)") (class "Default")
      (node (ref "B1") (pin "A0") (pinfunction "A0_A0") (pintype "bidirectional"))
    )
    (net (code "71") (name "unconnected-(B1-PadA1)") (class "Default")
      (node (ref "B1") (pin "A1") (pinfunction "A1_A1") (pintype "bidirectional"))
    )
    (net (code "72") (name "unconnected-(B1-PadA2)") (class "Default")
      (node (ref "B1") (pin "A2") (pinfunction "A2_A2") (pintype "bidirectional"))
    )
    (net (code "73") (name "unconnected-(B1-PadA3)") (class "Default")
      (node (ref "B1") (pin "A3") (pinfunction "A3_A3") (pintype "bidirectional"))
    )
    (net (code "74") (name "unconnected-(B1-PadA4)") (class "Default")
      (node (ref "B1") (pin "A4") (pinfunction "A4_A4") (pintype "bidirectional"))
    )
    (net (code "75") (name "unconnected-(B1-PadA5)") (class "Default")
      (node (ref "B1") (pin "A5") (pinfunction "A5_A5") (pintype "bidirectional"))
    )
    (net (code "76") (name "unconnected-(B1-PadAREF)") (class "Default")
      (node (ref "B1") (pin "AREF") (pinfunction "AREF_AREF") (pintype "bidirectional"))
    )
    (net (code "77") (name "unconnected-(B1-PadD2)") (class "Default")
      (node (ref "B1") (pin "D2") (pinfunction "D2_D2") (pintype "bidirectional"))
    )
    (net (code "78") (name "unconnected-(B1-PadD4)") (class "Default")
      (node (ref "B1") (pin "D4") (pinfunction "D4_D4") (pintype "bidirectional"))
    )
    (net (code "79") (name "unconnected-(B1-PadD7)") (class "Default")
      (node (ref "B1") (pin "D7") (pinfunction "D7_D7") (pintype "bidirectional"))
    )
    (net (code "80") (name "unconnected-(B1-PadD8)") (class "Default")
      (node (ref "B1") (pin "D8") (pinfunction "D8_D8") (pintype "bidirectional"))
    )
    (net (code "81") (name "unconnected-(B1-PadIOREF)") (class "Default")
      (node (ref "B1") (pin "IOREF") (pinfunction "IOREF_IOREF") (pintype "bidirectional"))
    )
    (net (code "82") (name "unconnected-(B1-PadRES)") (class "Default")
      (node (ref "B1") (pin "RES") (pinfunction "RES_RES") (pintype "bidirectional"))
    )
    (net (code "83") (name "unconnected-(J5-Pad7)") (class "Default")
      (node (ref "J5") (pin "7") (pinfunction "7_7") (pintype "passive"))
    )
    (net (code "84") (name "unconnected-(J6-Pad8)") (class "Default")
      (node (ref "J6") (pin "8") (pinfunction "8_8") (pintype "passive"))
    )
    (net (code "85") (name "unconnected-(U1-D1--Pad8)") (class "Default")
      (node (ref "U1") (pin "8") (pinfunction "D1-_8") (pintype "bidirectional"))
    )
    (net (code "86") (name "unconnected-(U3-IO1-Pad1)") (class "Default")
      (node (ref "U3") (pin "1") (pinfunction "IO1_1") (pintype "bidirectional"))
    )
    (net (code "87") (name "unconnected-(U3-IO2-Pad3)") (class "Default")
      (node (ref "U3") (pin "3") (pinfunction "IO2_3") (pintype "bidirectional"))
    )
    (net (code "88") (name "unconnected-(U4-CBUS0-Pad18)") (class "Default")
      (node (ref "U4") (pin "18") (pinfunction "CBUS0_18") (pintype "bidirectional"))
    )
    (net (code "89") (name "unconnected-(U4-CBUS1-Pad17)") (class "Default")
      (node (ref "U4") (pin "17") (pinfunction "CBUS1_17") (pintype "bidirectional"))
    )
    (net (code "90") (name "unconnected-(U4-CBUS2-Pad10)") (class "Default")
      (node (ref "U4") (pin "10") (pinfunction "CBUS2_10") (pintype "bidirectional"))
    )
    (net (code "91") (name "unconnected-(U4-CBUS3-Pad19)") (class "Default")
      (node (ref "U4") (pin "19") (pinfunction "CBUS3_19") (pintype "bidirectional"))
    )
    (net (code "92") (name "unconnected-(U4-~{DCD}-Pad8)") (class "Default")
      (node (ref "U4") (pin "8") (pinfunction "~{DCD}_8") (pintype "bidirectional"))
    )
    (net (code "93") (name "unconnected-(U4-~{DSR}-Pad7)") (class "Default")
      (node (ref "U4") (pin "7") (pinfunction "~{DSR}_7") (pintype "bidirectional"))
    )
    (net (code "94") (name "unconnected-(U4-~{RI}-Pad5)") (class "Default")
      (node (ref "U4") (pin "5") (pinfunction "~{RI}_5") (pintype "bidirectional"))
    )
    (net (code "95") (name "unconnected-(U5-IO1-Pad1)") (class "Default")
      (node (ref "U5") (pin "1") (pinfunction "IO1_1") (pintype "bidirectional"))
    )
    (net (code "96") (name "unconnected-(U5-IO2-Pad3)") (class "Default")
      (node (ref "U5") (pin "3") (pinfunction "IO2_3") (pintype "bidirectional"))
    )
  )
)
